# AfternoonCape_RevA3_6chan.net
KiCad netlist of a schematic drawn in Altium Designer
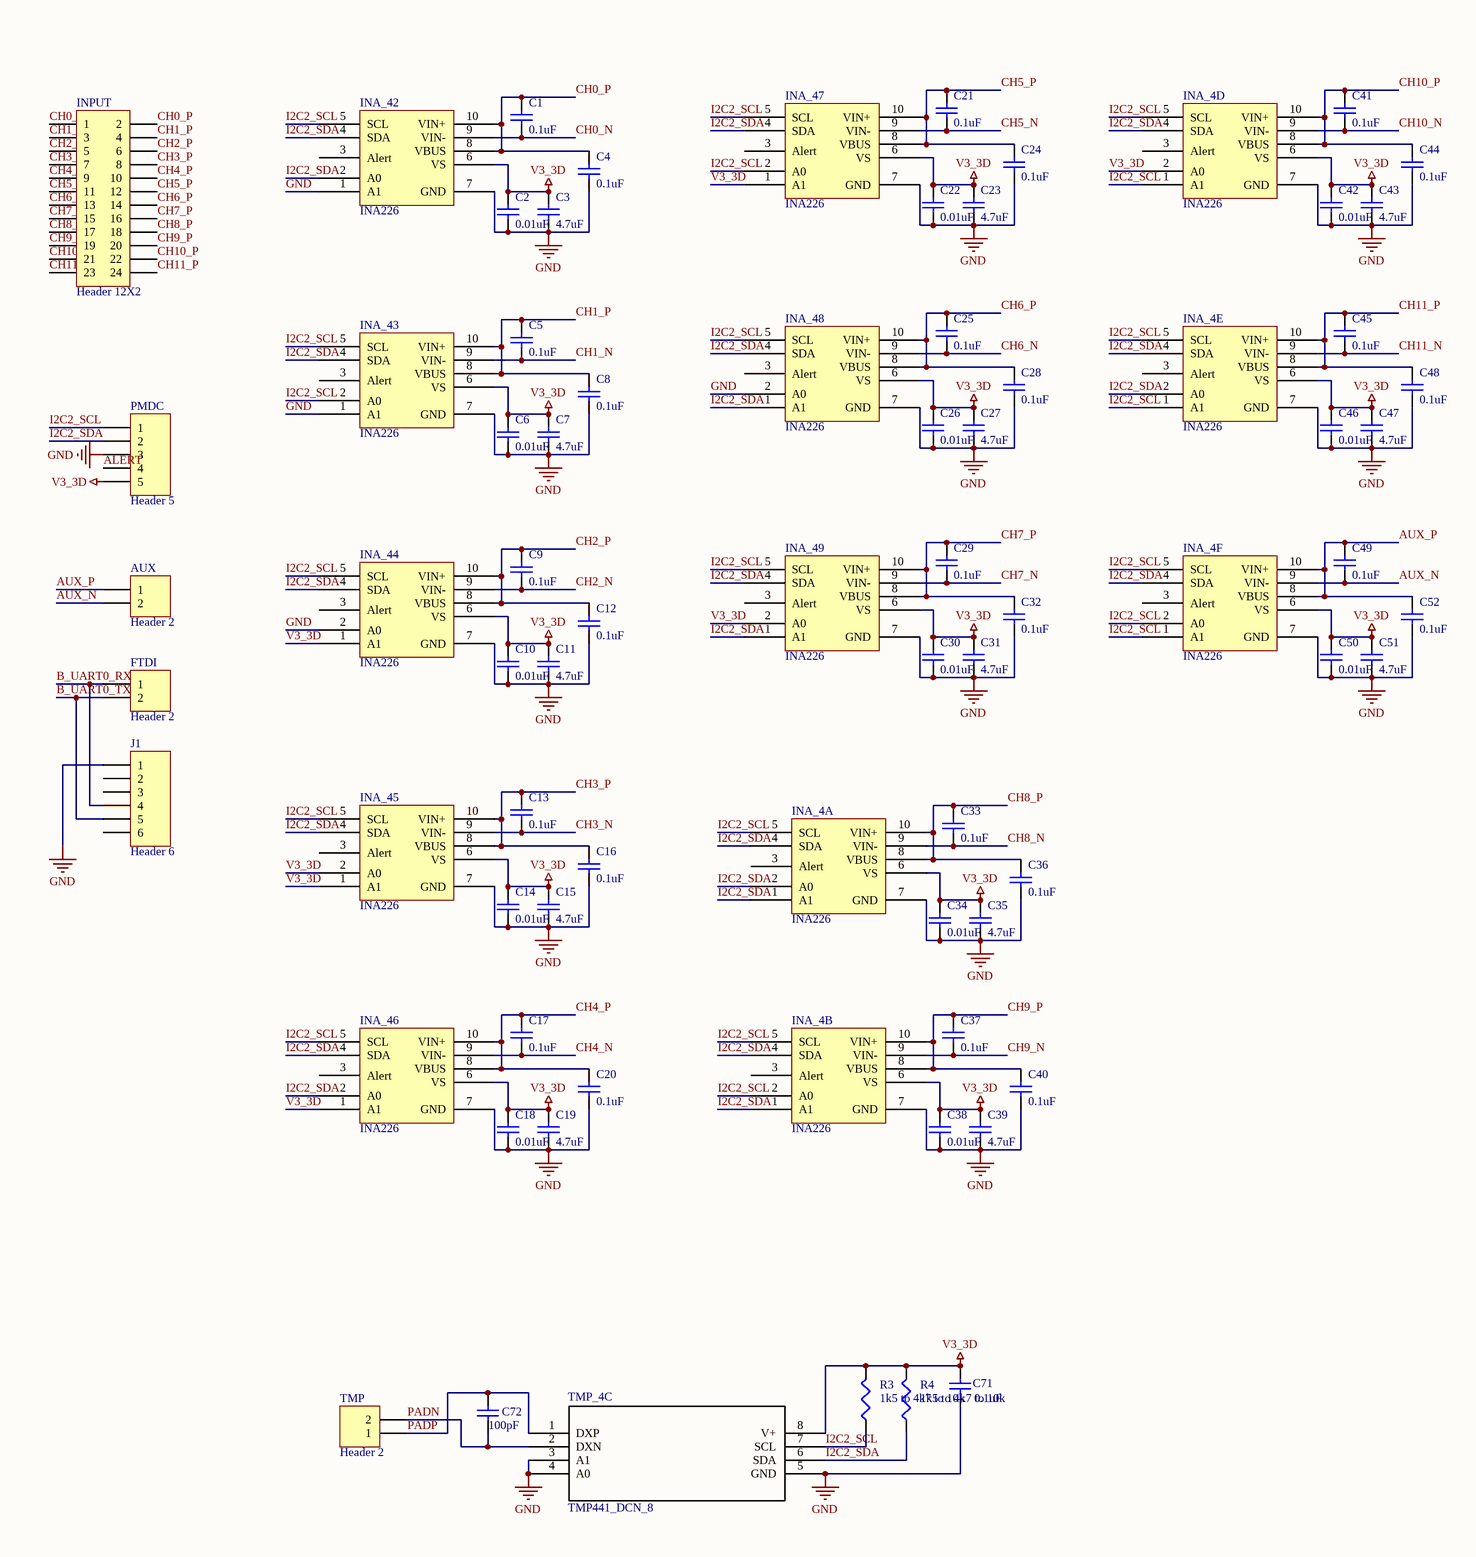
[diagram p0: AfternoonCape_RevA3_6chan.SchDoc, left]
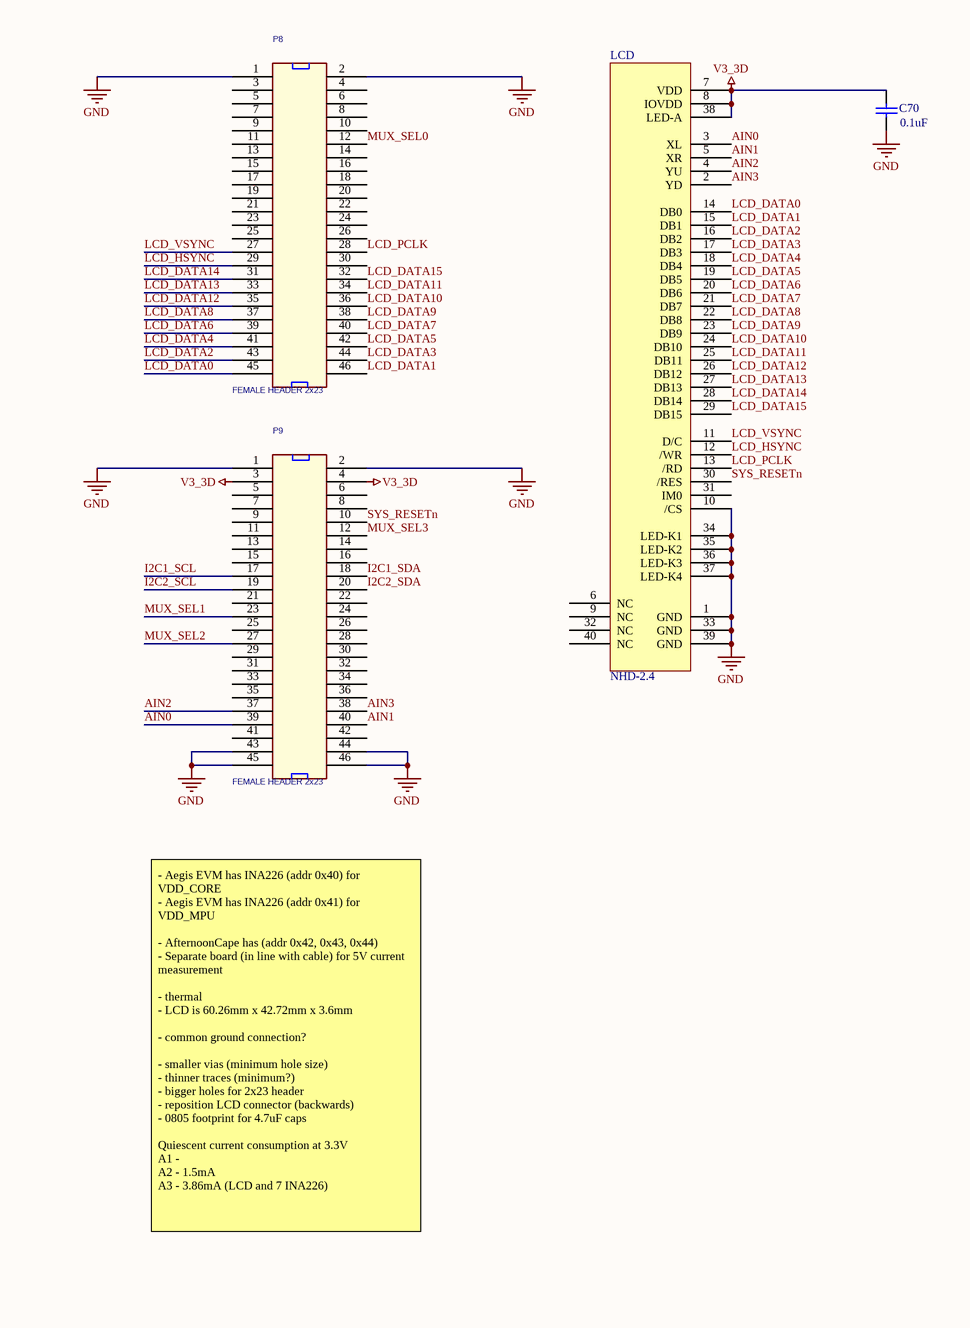
[diagram p1: AfternoonCape_RevA3_6chan.SchDoc, right]

(export (version "E")
  (design (tool "Eeschema 10.0.6"))
  (components
    (comp (ref "AUX")
      (value "Header 2")
      (footprint "HDR1X2")
      (description "Header, 2-Pin")
      (fields (field (name "PUBLISHER") "Altium Limited"))
      (libsource (lib "Miscellaneous Connectors") (part "Header 2"))
    )
    (comp (ref "C1")
      (value "0.1uF")
      (footprint "0402")
      (description "Capacitor (Semiconductor SIM Model)")
      (fields (field (name "Comment") "Cap Semi") (field (name "PUBLISHER") "Altium Limited"))
      (libsource (lib "Miscellaneous Devices") (part "Cap Semi"))
    )
    (comp (ref "C2")
      (value "0.01uF")
      (footprint "0402")
      (description "Capacitor (Semiconductor SIM Model)")
      (fields (field (name "Comment") "Cap Semi") (field (name "PUBLISHER") "Altium Limited"))
      (libsource (lib "Miscellaneous Devices") (part "Cap Semi"))
    )
    (comp (ref "C3")
      (value "4.7uF")
      (footprint "0402")
      (description "Capacitor (Semiconductor SIM Model)")
      (fields (field (name "Comment") "Cap Semi") (field (name "PUBLISHER") "Altium Limited"))
      (libsource (lib "Miscellaneous Devices") (part "Cap Semi"))
    )
    (comp (ref "C4")
      (value "0.1uF")
      (footprint "0402")
      (description "Capacitor (Semiconductor SIM Model)")
      (fields (field (name "Comment") "Cap Semi") (field (name "PUBLISHER") "Altium Limited"))
      (libsource (lib "Miscellaneous Devices") (part "Cap Semi"))
    )
    (comp (ref "C5")
      (value "0.1uF")
      (footprint "0402")
      (description "Capacitor (Semiconductor SIM Model)")
      (fields (field (name "Comment") "Cap Semi") (field (name "PUBLISHER") "Altium Limited"))
      (libsource (lib "Miscellaneous Devices") (part "Cap Semi"))
    )
    (comp (ref "C6")
      (value "0.01uF")
      (footprint "0402")
      (description "Capacitor (Semiconductor SIM Model)")
      (fields (field (name "Comment") "Cap Semi") (field (name "PUBLISHER") "Altium Limited"))
      (libsource (lib "Miscellaneous Devices") (part "Cap Semi"))
    )
    (comp (ref "C7")
      (value "4.7uF")
      (footprint "0402")
      (description "Capacitor (Semiconductor SIM Model)")
      (fields (field (name "Comment") "Cap Semi") (field (name "PUBLISHER") "Altium Limited"))
      (libsource (lib "Miscellaneous Devices") (part "Cap Semi"))
    )
    (comp (ref "C8")
      (value "0.1uF")
      (footprint "0402")
      (description "Capacitor (Semiconductor SIM Model)")
      (fields (field (name "Comment") "Cap Semi") (field (name "PUBLISHER") "Altium Limited"))
      (libsource (lib "Miscellaneous Devices") (part "Cap Semi"))
    )
    (comp (ref "C9")
      (value "0.1uF")
      (footprint "0402")
      (description "Capacitor (Semiconductor SIM Model)")
      (fields (field (name "Comment") "Cap Semi") (field (name "PUBLISHER") "Altium Limited"))
      (libsource (lib "Miscellaneous Devices") (part "Cap Semi"))
    )
    (comp (ref "C10")
      (value "0.01uF")
      (footprint "0402")
      (description "Capacitor (Semiconductor SIM Model)")
      (fields (field (name "Comment") "Cap Semi") (field (name "PUBLISHER") "Altium Limited"))
      (libsource (lib "Miscellaneous Devices") (part "Cap Semi"))
    )
    (comp (ref "C11")
      (value "4.7uF")
      (footprint "0402")
      (description "Capacitor (Semiconductor SIM Model)")
      (fields (field (name "Comment") "Cap Semi") (field (name "PUBLISHER") "Altium Limited"))
      (libsource (lib "Miscellaneous Devices") (part "Cap Semi"))
    )
    (comp (ref "C12")
      (value "0.1uF")
      (footprint "0402")
      (description "Capacitor (Semiconductor SIM Model)")
      (fields (field (name "Comment") "Cap Semi") (field (name "PUBLISHER") "Altium Limited"))
      (libsource (lib "Miscellaneous Devices") (part "Cap Semi"))
    )
    (comp (ref "C13")
      (value "0.1uF")
      (footprint "0402")
      (description "Capacitor (Semiconductor SIM Model)")
      (fields (field (name "Comment") "Cap Semi") (field (name "PUBLISHER") "Altium Limited"))
      (libsource (lib "Miscellaneous Devices") (part "Cap Semi"))
    )
    (comp (ref "C14")
      (value "0.01uF")
      (footprint "0402")
      (description "Capacitor (Semiconductor SIM Model)")
      (fields (field (name "Comment") "Cap Semi") (field (name "PUBLISHER") "Altium Limited"))
      (libsource (lib "Miscellaneous Devices") (part "Cap Semi"))
    )
    (comp (ref "C15")
      (value "4.7uF")
      (footprint "0402")
      (description "Capacitor (Semiconductor SIM Model)")
      (fields (field (name "Comment") "Cap Semi") (field (name "PUBLISHER") "Altium Limited"))
      (libsource (lib "Miscellaneous Devices") (part "Cap Semi"))
    )
    (comp (ref "C16")
      (value "0.1uF")
      (footprint "0402")
      (description "Capacitor (Semiconductor SIM Model)")
      (fields (field (name "Comment") "Cap Semi") (field (name "PUBLISHER") "Altium Limited"))
      (libsource (lib "Miscellaneous Devices") (part "Cap Semi"))
    )
    (comp (ref "C17")
      (value "0.1uF")
      (footprint "0402")
      (description "Capacitor (Semiconductor SIM Model)")
      (fields (field (name "Comment") "Cap Semi") (field (name "PUBLISHER") "Altium Limited"))
      (libsource (lib "Miscellaneous Devices") (part "Cap Semi"))
    )
    (comp (ref "C18")
      (value "0.01uF")
      (footprint "0402")
      (description "Capacitor (Semiconductor SIM Model)")
      (fields (field (name "Comment") "Cap Semi") (field (name "PUBLISHER") "Altium Limited"))
      (libsource (lib "Miscellaneous Devices") (part "Cap Semi"))
    )
    (comp (ref "C19")
      (value "4.7uF")
      (footprint "0402")
      (description "Capacitor (Semiconductor SIM Model)")
      (fields (field (name "Comment") "Cap Semi") (field (name "PUBLISHER") "Altium Limited"))
      (libsource (lib "Miscellaneous Devices") (part "Cap Semi"))
    )
    (comp (ref "C20")
      (value "0.1uF")
      (footprint "0402")
      (description "Capacitor (Semiconductor SIM Model)")
      (fields (field (name "Comment") "Cap Semi") (field (name "PUBLISHER") "Altium Limited"))
      (libsource (lib "Miscellaneous Devices") (part "Cap Semi"))
    )
    (comp (ref "C21")
      (value "0.1uF")
      (footprint "0402")
      (description "Capacitor (Semiconductor SIM Model)")
      (fields (field (name "Comment") "Cap Semi") (field (name "PUBLISHER") "Altium Limited"))
      (libsource (lib "Miscellaneous Devices") (part "Cap Semi"))
    )
    (comp (ref "C22")
      (value "0.01uF")
      (footprint "0402")
      (description "Capacitor (Semiconductor SIM Model)")
      (fields (field (name "Comment") "Cap Semi") (field (name "PUBLISHER") "Altium Limited"))
      (libsource (lib "Miscellaneous Devices") (part "Cap Semi"))
    )
    (comp (ref "C23")
      (value "4.7uF")
      (footprint "0402")
      (description "Capacitor (Semiconductor SIM Model)")
      (fields (field (name "Comment") "Cap Semi") (field (name "PUBLISHER") "Altium Limited"))
      (libsource (lib "Miscellaneous Devices") (part "Cap Semi"))
    )
    (comp (ref "C24")
      (value "0.1uF")
      (footprint "0402")
      (description "Capacitor (Semiconductor SIM Model)")
      (fields (field (name "Comment") "Cap Semi") (field (name "PUBLISHER") "Altium Limited"))
      (libsource (lib "Miscellaneous Devices") (part "Cap Semi"))
    )
    (comp (ref "C25")
      (value "0.1uF")
      (footprint "0402")
      (description "Capacitor (Semiconductor SIM Model)")
      (fields (field (name "Comment") "Cap Semi") (field (name "PUBLISHER") "Altium Limited"))
      (libsource (lib "Miscellaneous Devices") (part "Cap Semi"))
    )
    (comp (ref "C26")
      (value "0.01uF")
      (footprint "0402")
      (description "Capacitor (Semiconductor SIM Model)")
      (fields (field (name "Comment") "Cap Semi") (field (name "PUBLISHER") "Altium Limited"))
      (libsource (lib "Miscellaneous Devices") (part "Cap Semi"))
    )
    (comp (ref "C27")
      (value "4.7uF")
      (footprint "0402")
      (description "Capacitor (Semiconductor SIM Model)")
      (fields (field (name "Comment") "Cap Semi") (field (name "PUBLISHER") "Altium Limited"))
      (libsource (lib "Miscellaneous Devices") (part "Cap Semi"))
    )
    (comp (ref "C28")
      (value "0.1uF")
      (footprint "0402")
      (description "Capacitor (Semiconductor SIM Model)")
      (fields (field (name "Comment") "Cap Semi") (field (name "PUBLISHER") "Altium Limited"))
      (libsource (lib "Miscellaneous Devices") (part "Cap Semi"))
    )
    (comp (ref "C29")
      (value "0.1uF")
      (footprint "0402")
      (description "Capacitor (Semiconductor SIM Model)")
      (fields (field (name "Comment") "Cap Semi") (field (name "PUBLISHER") "Altium Limited"))
      (libsource (lib "Miscellaneous Devices") (part "Cap Semi"))
    )
    (comp (ref "C30")
      (value "0.01uF")
      (footprint "0402")
      (description "Capacitor (Semiconductor SIM Model)")
      (fields (field (name "Comment") "Cap Semi") (field (name "PUBLISHER") "Altium Limited"))
      (libsource (lib "Miscellaneous Devices") (part "Cap Semi"))
    )
    (comp (ref "C31")
      (value "4.7uF")
      (footprint "0402")
      (description "Capacitor (Semiconductor SIM Model)")
      (fields (field (name "Comment") "Cap Semi") (field (name "PUBLISHER") "Altium Limited"))
      (libsource (lib "Miscellaneous Devices") (part "Cap Semi"))
    )
    (comp (ref "C32")
      (value "0.1uF")
      (footprint "0402")
      (description "Capacitor (Semiconductor SIM Model)")
      (fields (field (name "Comment") "Cap Semi") (field (name "PUBLISHER") "Altium Limited"))
      (libsource (lib "Miscellaneous Devices") (part "Cap Semi"))
    )
    (comp (ref "C33")
      (value "0.1uF")
      (footprint "0402")
      (description "Capacitor (Semiconductor SIM Model)")
      (fields (field (name "Comment") "Cap Semi") (field (name "PUBLISHER") "Altium Limited"))
      (libsource (lib "Miscellaneous Devices") (part "Cap Semi"))
    )
    (comp (ref "C34")
      (value "0.01uF")
      (footprint "0402")
      (description "Capacitor (Semiconductor SIM Model)")
      (fields (field (name "Comment") "Cap Semi") (field (name "PUBLISHER") "Altium Limited"))
      (libsource (lib "Miscellaneous Devices") (part "Cap Semi"))
    )
    (comp (ref "C35")
      (value "4.7uF")
      (footprint "0402")
      (description "Capacitor (Semiconductor SIM Model)")
      (fields (field (name "Comment") "Cap Semi") (field (name "PUBLISHER") "Altium Limited"))
      (libsource (lib "Miscellaneous Devices") (part "Cap Semi"))
    )
    (comp (ref "C36")
      (value "0.1uF")
      (footprint "0402")
      (description "Capacitor (Semiconductor SIM Model)")
      (fields (field (name "Comment") "Cap Semi") (field (name "PUBLISHER") "Altium Limited"))
      (libsource (lib "Miscellaneous Devices") (part "Cap Semi"))
    )
    (comp (ref "C37")
      (value "0.1uF")
      (footprint "0402")
      (description "Capacitor (Semiconductor SIM Model)")
      (fields (field (name "Comment") "Cap Semi") (field (name "PUBLISHER") "Altium Limited"))
      (libsource (lib "Miscellaneous Devices") (part "Cap Semi"))
    )
    (comp (ref "C38")
      (value "0.01uF")
      (footprint "0402")
      (description "Capacitor (Semiconductor SIM Model)")
      (fields (field (name "Comment") "Cap Semi") (field (name "PUBLISHER") "Altium Limited"))
      (libsource (lib "Miscellaneous Devices") (part "Cap Semi"))
    )
    (comp (ref "C39")
      (value "4.7uF")
      (footprint "0402")
      (description "Capacitor (Semiconductor SIM Model)")
      (fields (field (name "Comment") "Cap Semi") (field (name "PUBLISHER") "Altium Limited"))
      (libsource (lib "Miscellaneous Devices") (part "Cap Semi"))
    )
    (comp (ref "C40")
      (value "0.1uF")
      (footprint "0402")
      (description "Capacitor (Semiconductor SIM Model)")
      (fields (field (name "Comment") "Cap Semi") (field (name "PUBLISHER") "Altium Limited"))
      (libsource (lib "Miscellaneous Devices") (part "Cap Semi"))
    )
    (comp (ref "C41")
      (value "0.1uF")
      (footprint "0402")
      (description "Capacitor (Semiconductor SIM Model)")
      (fields (field (name "Comment") "Cap Semi") (field (name "PUBLISHER") "Altium Limited"))
      (libsource (lib "Miscellaneous Devices") (part "Cap Semi"))
    )
    (comp (ref "C42")
      (value "0.01uF")
      (footprint "0402")
      (description "Capacitor (Semiconductor SIM Model)")
      (fields (field (name "Comment") "Cap Semi") (field (name "PUBLISHER") "Altium Limited"))
      (libsource (lib "Miscellaneous Devices") (part "Cap Semi"))
    )
    (comp (ref "C43")
      (value "4.7uF")
      (footprint "0402")
      (description "Capacitor (Semiconductor SIM Model)")
      (fields (field (name "Comment") "Cap Semi") (field (name "PUBLISHER") "Altium Limited"))
      (libsource (lib "Miscellaneous Devices") (part "Cap Semi"))
    )
    (comp (ref "C44")
      (value "0.1uF")
      (footprint "0402")
      (description "Capacitor (Semiconductor SIM Model)")
      (fields (field (name "Comment") "Cap Semi") (field (name "PUBLISHER") "Altium Limited"))
      (libsource (lib "Miscellaneous Devices") (part "Cap Semi"))
    )
    (comp (ref "C45")
      (value "0.1uF")
      (footprint "0402")
      (description "Capacitor (Semiconductor SIM Model)")
      (fields (field (name "Comment") "Cap Semi") (field (name "PUBLISHER") "Altium Limited"))
      (libsource (lib "Miscellaneous Devices") (part "Cap Semi"))
    )
    (comp (ref "C46")
      (value "0.01uF")
      (footprint "0402")
      (description "Capacitor (Semiconductor SIM Model)")
      (fields (field (name "Comment") "Cap Semi") (field (name "PUBLISHER") "Altium Limited"))
      (libsource (lib "Miscellaneous Devices") (part "Cap Semi"))
    )
    (comp (ref "C47")
      (value "4.7uF")
      (footprint "0402")
      (description "Capacitor (Semiconductor SIM Model)")
      (fields (field (name "Comment") "Cap Semi") (field (name "PUBLISHER") "Altium Limited"))
      (libsource (lib "Miscellaneous Devices") (part "Cap Semi"))
    )
    (comp (ref "C48")
      (value "0.1uF")
      (footprint "0402")
      (description "Capacitor (Semiconductor SIM Model)")
      (fields (field (name "Comment") "Cap Semi") (field (name "PUBLISHER") "Altium Limited"))
      (libsource (lib "Miscellaneous Devices") (part "Cap Semi"))
    )
    (comp (ref "C49")
      (value "0.1uF")
      (footprint "0402")
      (description "Capacitor (Semiconductor SIM Model)")
      (fields (field (name "Comment") "Cap Semi") (field (name "PUBLISHER") "Altium Limited"))
      (libsource (lib "Miscellaneous Devices") (part "Cap Semi"))
    )
    (comp (ref "C50")
      (value "0.01uF")
      (footprint "0402")
      (description "Capacitor (Semiconductor SIM Model)")
      (fields (field (name "Comment") "Cap Semi") (field (name "PUBLISHER") "Altium Limited"))
      (libsource (lib "Miscellaneous Devices") (part "Cap Semi"))
    )
    (comp (ref "C51")
      (value "4.7uF")
      (footprint "0402")
      (description "Capacitor (Semiconductor SIM Model)")
      (fields (field (name "Comment") "Cap Semi") (field (name "PUBLISHER") "Altium Limited"))
      (libsource (lib "Miscellaneous Devices") (part "Cap Semi"))
    )
    (comp (ref "C52")
      (value "0.1uF")
      (footprint "0402")
      (description "Capacitor (Semiconductor SIM Model)")
      (fields (field (name "Comment") "Cap Semi") (field (name "PUBLISHER") "Altium Limited"))
      (libsource (lib "Miscellaneous Devices") (part "Cap Semi"))
    )
    (comp (ref "C70")
      (value "0.1uF")
      (footprint "0402")
      (description "Capacitor (Semiconductor SIM Model)")
      (fields (field (name "Comment") "Cap Semi") (field (name "PUBLISHER") "Altium Limited"))
      (libsource (lib "Miscellaneous Devices") (part "Cap Semi"))
    )
    (comp (ref "C71")
      (value "0.1uF")
      (footprint "0402")
      (description "Capacitor (Semiconductor SIM Model)")
      (fields (field (name "Comment") "Cap Semi") (field (name "PUBLISHER") "Altium Limited"))
      (libsource (lib "Miscellaneous Devices") (part "Cap Semi"))
    )
    (comp (ref "C72")
      (value "100pF")
      (footprint "0402")
      (description "Capacitor (Semiconductor SIM Model)")
      (fields (field (name "Comment") "Cap Semi") (field (name "PUBLISHER") "Altium Limited"))
      (libsource (lib "Miscellaneous Devices") (part "Cap Semi"))
    )
    (comp (ref "FTDI")
      (value "Header 2")
      (footprint "HDR1X2")
      (description "Header, 2-Pin")
      (fields (field (name "PUBLISHER") "Altium Limited"))
      (libsource (lib "Miscellaneous Connectors") (part "Header 2"))
    )
    (comp (ref "INA_4A") (value "INA226") (footprint "DGS10") (libsource (lib "INA226") (part "INA226")))
    (comp (ref "INA_4B") (value "INA226") (footprint "DGS10") (libsource (lib "INA226") (part "INA226")))
    (comp (ref "INA_4D") (value "INA226") (footprint "DGS10") (libsource (lib "INA226") (part "INA226")))
    (comp (ref "INA_4E") (value "INA226") (footprint "DGS10") (libsource (lib "INA226") (part "INA226")))
    (comp (ref "INA_4F") (value "INA226") (footprint "DGS10") (libsource (lib "INA226") (part "INA226")))
    (comp (ref "INA_42") (value "INA226") (footprint "DGS10") (libsource (lib "INA226") (part "INA226")))
    (comp (ref "INA_43") (value "INA226") (footprint "DGS10") (libsource (lib "INA226") (part "INA226")))
    (comp (ref "INA_44") (value "INA226") (footprint "DGS10") (libsource (lib "INA226") (part "INA226")))
    (comp (ref "INA_45") (value "INA226") (footprint "DGS10") (libsource (lib "INA226") (part "INA226")))
    (comp (ref "INA_46") (value "INA226") (footprint "DGS10") (libsource (lib "INA226") (part "INA226")))
    (comp (ref "INA_47") (value "INA226") (footprint "DGS10") (libsource (lib "INA226") (part "INA226")))
    (comp (ref "INA_48") (value "INA226") (footprint "DGS10") (libsource (lib "INA226") (part "INA226")))
    (comp (ref "INA_49") (value "INA226") (footprint "DGS10") (libsource (lib "INA226") (part "INA226")))
    (comp (ref "INPUT")
      (value "Header 12X2")
      (footprint "HDR2X12")
      (description "Header, 12-Pin, Dual row")
      (fields (field (name "PUBLISHER") "Altium Limited"))
      (libsource (lib "Miscellaneous Connectors") (part "Header 12X2"))
    )
    (comp (ref "J1")
      (value "Header 6")
      (footprint "HDR1X6")
      (description "6-pin female header, long legs for FTDI-USB cable")
      (fields (field (name "PUBLISHER") "Altium Limited"))
      (libsource (lib "Miscellaneous Connectors") (part "Header 6"))
    )
    (comp (ref "LCD")
      (value "NHD-2.4")
      (footprint "NHD-2.4")
      (description "2.4\" LCD NHD-2.4-240320SF-CTXL#-FTN1 54132-4062 Molex LCD Connector Footprint")
      (libsource (lib "Sitara_PowerMonitorCape") (part "NHD-2.4"))
    )
    (comp (ref "P8")
      (value "FEMALE HEADER 2x23")
      (description "CONN HEADER FMAL 46PS.1\" DL GOLD")
      (fields
        (field (name "MANUFACTURER") "Sullins Connector Solutions")
        (field (name "MANUFACTURER PART NUMBER") "PPPC232LFBN-RC")
      )
      (libsource (lib "BEAGLEBONEBLACK_REV A5B") (part "HDR_46_F_2_0.1_0.1"))
    )
    (comp (ref "P9")
      (value "FEMALE HEADER 2x23")
      (description "CONN HEADER FMAL 46PS.1\" DL GOLD")
      (fields
        (field (name "MANUFACTURER") "Sullins Connector Solutions")
        (field (name "MANUFACTURER PART NUMBER") "PPPC232LFBN-RC")
      )
      (libsource (lib "BEAGLEBONEBLACK_REV A5B") (part "HDR_46_F_2_0.1_0.1"))
    )
    (comp (ref "PMDC")
      (value "Header 5")
      (footprint "HDR1X5")
      (description "Header, 5-Pin")
      (fields (field (name "PUBLISHER") "Altium Limited"))
      (libsource (lib "Miscellaneous Connectors") (part "Header 5"))
    )
    (comp (ref "R3")
      (value "1k5 to 4k7 to 10k")
      (footprint "0402")
      (description "Resistor")
      (fields (field (name "Comment") "Res3") (field (name "PUBLISHER") "Altium Limited"))
      (libsource (lib "Miscellaneous Devices") (part "Res3"))
    )
    (comp (ref "R4")
      (value "1k5 to 4k7 to 10k")
      (footprint "0402")
      (description "Resistor")
      (fields (field (name "Comment") "Res3") (field (name "PUBLISHER") "Altium Limited"))
      (libsource (lib "Miscellaneous Devices") (part "Res3"))
    )
    (comp (ref "TMP")
      (value "Header 2")
      (footprint "HDR1X2")
      (description "Header, 2-Pin")
      (fields (field (name "PUBLISHER") "Altium Limited"))
      (libsource (lib "") (part "Header 2_1"))
    )
    (comp (ref "TMP_4C")
      (value "TMP441_DCN_8")
      (footprint "TMP441:DCN8-L")
      (description "Imported")
      (fields
        (field (name "MANUFACTURER_PART_NUMBER") "tmp441_dcn_8")
        (field (name "GENERIC_PART_NUMBER") "TMP441")
      )
      (libsource (lib "TMP441") (part "TMP441_DCN_8"))
    )
  )
  (nets
    (net (code "1") (name "/AIN0") (class "Default")
      (node (ref "LCD") (pin "3") (pinfunction "XL_3") (pintype "passive"))
      (node (ref "P9") (pin "39") (pinfunction "20_39") (pintype "passive"))
    )
    (net (code "2") (name "/AIN1") (class "Default")
      (node (ref "LCD") (pin "5") (pinfunction "XR_5") (pintype "passive"))
      (node (ref "P9") (pin "40") (pinfunction "45_40") (pintype "passive"))
    )
    (net (code "3") (name "/AIN2") (class "Default")
      (node (ref "LCD") (pin "4") (pinfunction "YU_4") (pintype "passive"))
      (node (ref "P9") (pin "37") (pinfunction "19_37") (pintype "passive"))
    )
    (net (code "4") (name "/AIN3") (class "Default")
      (node (ref "LCD") (pin "2") (pinfunction "YD_2") (pintype "passive"))
      (node (ref "P9") (pin "38") (pinfunction "44_38") (pintype "passive"))
    )
    (net (code "5") (name "/ALERT") (class "Default")
      (node (ref "PMDC") (pin "4") (pinfunction "4_4") (pintype "passive"))
    )
    (net (code "6") (name "/AUX_N") (class "Default")
      (node (ref "AUX") (pin "2") (pinfunction "2_2") (pintype "passive"))
      (node (ref "C49") (pin "1") (pinfunction "1_1") (pintype "passive"))
      (node (ref "INA_4F") (pin "9") (pinfunction "VIN-_9") (pintype "passive"))
    )
    (net (code "7") (name "/AUX_P") (class "Default")
      (node (ref "AUX") (pin "1") (pinfunction "1_1") (pintype "passive"))
      (node (ref "C49") (pin "2") (pinfunction "2_2") (pintype "passive"))
      (node (ref "C52") (pin "2") (pinfunction "2_2") (pintype "passive"))
      (node (ref "INA_4F") (pin "10") (pinfunction "VIN+_10") (pintype "passive"))
      (node (ref "INA_4F") (pin "8") (pinfunction "VBUS_8") (pintype "passive"))
    )
    (net (code "8") (name "/B_UART0_RX") (class "Default")
      (node (ref "FTDI") (pin "1") (pinfunction "1_1") (pintype "passive"))
      (node (ref "J1") (pin "4") (pinfunction "4_4") (pintype "passive"))
    )
    (net (code "9") (name "/B_UART0_TX") (class "Default")
      (node (ref "FTDI") (pin "2") (pinfunction "2_2") (pintype "passive"))
      (node (ref "J1") (pin "5") (pinfunction "5_5") (pintype "passive"))
    )
    (net (code "10") (name "/CH0_N") (class "Default")
      (node (ref "C1") (pin "1") (pinfunction "1_1") (pintype "passive"))
      (node (ref "INA_42") (pin "9") (pinfunction "VIN-_9") (pintype "passive"))
      (node (ref "INPUT") (pin "1") (pinfunction "1_1") (pintype "passive"))
    )
    (net (code "11") (name "/CH0_P") (class "Default")
      (node (ref "C1") (pin "2") (pinfunction "2_2") (pintype "passive"))
      (node (ref "C4") (pin "2") (pinfunction "2_2") (pintype "passive"))
      (node (ref "INA_42") (pin "10") (pinfunction "VIN+_10") (pintype "passive"))
      (node (ref "INA_42") (pin "8") (pinfunction "VBUS_8") (pintype "passive"))
      (node (ref "INPUT") (pin "2") (pinfunction "2_2") (pintype "passive"))
    )
    (net (code "12") (name "/CH1_N") (class "Default")
      (node (ref "C5") (pin "1") (pinfunction "1_1") (pintype "passive"))
      (node (ref "INA_43") (pin "9") (pinfunction "VIN-_9") (pintype "passive"))
      (node (ref "INPUT") (pin "3") (pinfunction "3_3") (pintype "passive"))
    )
    (net (code "13") (name "/CH1_P") (class "Default")
      (node (ref "C5") (pin "2") (pinfunction "2_2") (pintype "passive"))
      (node (ref "C8") (pin "2") (pinfunction "2_2") (pintype "passive"))
      (node (ref "INA_43") (pin "10") (pinfunction "VIN+_10") (pintype "passive"))
      (node (ref "INA_43") (pin "8") (pinfunction "VBUS_8") (pintype "passive"))
      (node (ref "INPUT") (pin "4") (pinfunction "4_4") (pintype "passive"))
    )
    (net (code "14") (name "/CH2_N") (class "Default")
      (node (ref "C9") (pin "1") (pinfunction "1_1") (pintype "passive"))
      (node (ref "INA_44") (pin "9") (pinfunction "VIN-_9") (pintype "passive"))
      (node (ref "INPUT") (pin "5") (pinfunction "5_5") (pintype "passive"))
    )
    (net (code "15") (name "/CH2_P") (class "Default")
      (node (ref "C12") (pin "2") (pinfunction "2_2") (pintype "passive"))
      (node (ref "C9") (pin "2") (pinfunction "2_2") (pintype "passive"))
      (node (ref "INA_44") (pin "10") (pinfunction "VIN+_10") (pintype "passive"))
      (node (ref "INA_44") (pin "8") (pinfunction "VBUS_8") (pintype "passive"))
      (node (ref "INPUT") (pin "6") (pinfunction "6_6") (pintype "passive"))
    )
    (net (code "16") (name "/CH3_N") (class "Default")
      (node (ref "C13") (pin "1") (pinfunction "1_1") (pintype "passive"))
      (node (ref "INA_45") (pin "9") (pinfunction "VIN-_9") (pintype "passive"))
      (node (ref "INPUT") (pin "7") (pinfunction "7_7") (pintype "passive"))
    )
    (net (code "17") (name "/CH3_P") (class "Default")
      (node (ref "C13") (pin "2") (pinfunction "2_2") (pintype "passive"))
      (node (ref "C16") (pin "2") (pinfunction "2_2") (pintype "passive"))
      (node (ref "INA_45") (pin "10") (pinfunction "VIN+_10") (pintype "passive"))
      (node (ref "INA_45") (pin "8") (pinfunction "VBUS_8") (pintype "passive"))
      (node (ref "INPUT") (pin "8") (pinfunction "8_8") (pintype "passive"))
    )
    (net (code "18") (name "/CH4_N") (class "Default")
      (node (ref "C17") (pin "1") (pinfunction "1_1") (pintype "passive"))
      (node (ref "INA_46") (pin "9") (pinfunction "VIN-_9") (pintype "passive"))
      (node (ref "INPUT") (pin "9") (pinfunction "9_9") (pintype "passive"))
    )
    (net (code "19") (name "/CH4_P") (class "Default")
      (node (ref "C17") (pin "2") (pinfunction "2_2") (pintype "passive"))
      (node (ref "C20") (pin "2") (pinfunction "2_2") (pintype "passive"))
      (node (ref "INA_46") (pin "10") (pinfunction "VIN+_10") (pintype "passive"))
      (node (ref "INA_46") (pin "8") (pinfunction "VBUS_8") (pintype "passive"))
      (node (ref "INPUT") (pin "10") (pinfunction "10_10") (pintype "passive"))
    )
    (net (code "20") (name "/CH5_N") (class "Default")
      (node (ref "C21") (pin "1") (pinfunction "1_1") (pintype "passive"))
      (node (ref "INA_47") (pin "9") (pinfunction "VIN-_9") (pintype "passive"))
      (node (ref "INPUT") (pin "11") (pinfunction "11_11") (pintype "passive"))
    )
    (net (code "21") (name "/CH5_P") (class "Default")
      (node (ref "C21") (pin "2") (pinfunction "2_2") (pintype "passive"))
      (node (ref "C24") (pin "2") (pinfunction "2_2") (pintype "passive"))
      (node (ref "INA_47") (pin "10") (pinfunction "VIN+_10") (pintype "passive"))
      (node (ref "INA_47") (pin "8") (pinfunction "VBUS_8") (pintype "passive"))
      (node (ref "INPUT") (pin "12") (pinfunction "12_12") (pintype "passive"))
    )
    (net (code "22") (name "/CH6_N") (class "Default")
      (node (ref "C25") (pin "1") (pinfunction "1_1") (pintype "passive"))
      (node (ref "INA_48") (pin "9") (pinfunction "VIN-_9") (pintype "passive"))
      (node (ref "INPUT") (pin "13") (pinfunction "13_13") (pintype "passive"))
    )
    (net (code "23") (name "/CH6_P") (class "Default")
      (node (ref "C25") (pin "2") (pinfunction "2_2") (pintype "passive"))
      (node (ref "C28") (pin "2") (pinfunction "2_2") (pintype "passive"))
      (node (ref "INA_48") (pin "10") (pinfunction "VIN+_10") (pintype "passive"))
      (node (ref "INA_48") (pin "8") (pinfunction "VBUS_8") (pintype "passive"))
      (node (ref "INPUT") (pin "14") (pinfunction "14_14") (pintype "passive"))
    )
    (net (code "24") (name "/CH7_N") (class "Default")
      (node (ref "C29") (pin "1") (pinfunction "1_1") (pintype "passive"))
      (node (ref "INA_49") (pin "9") (pinfunction "VIN-_9") (pintype "passive"))
      (node (ref "INPUT") (pin "15") (pinfunction "15_15") (pintype "passive"))
    )
    (net (code "25") (name "/CH7_P") (class "Default")
      (node (ref "C29") (pin "2") (pinfunction "2_2") (pintype "passive"))
      (node (ref "C32") (pin "2") (pinfunction "2_2") (pintype "passive"))
      (node (ref "INA_49") (pin "10") (pinfunction "VIN+_10") (pintype "passive"))
      (node (ref "INA_49") (pin "8") (pinfunction "VBUS_8") (pintype "passive"))
      (node (ref "INPUT") (pin "16") (pinfunction "16_16") (pintype "passive"))
    )
    (net (code "26") (name "/CH8_N") (class "Default")
      (node (ref "C33") (pin "1") (pinfunction "1_1") (pintype "passive"))
      (node (ref "INA_4A") (pin "9") (pinfunction "VIN-_9") (pintype "passive"))
      (node (ref "INPUT") (pin "17") (pinfunction "17_17") (pintype "passive"))
    )
    (net (code "27") (name "/CH8_P") (class "Default")
      (node (ref "C33") (pin "2") (pinfunction "2_2") (pintype "passive"))
      (node (ref "C36") (pin "2") (pinfunction "2_2") (pintype "passive"))
      (node (ref "INA_4A") (pin "10") (pinfunction "VIN+_10") (pintype "passive"))
      (node (ref "INA_4A") (pin "8") (pinfunction "VBUS_8") (pintype "passive"))
      (node (ref "INPUT") (pin "18") (pinfunction "18_18") (pintype "passive"))
    )
    (net (code "28") (name "/CH9_N") (class "Default")
      (node (ref "C37") (pin "1") (pinfunction "1_1") (pintype "passive"))
      (node (ref "INA_4B") (pin "9") (pinfunction "VIN-_9") (pintype "passive"))
      (node (ref "INPUT") (pin "19") (pinfunction "19_19") (pintype "passive"))
    )
    (net (code "29") (name "/CH9_P") (class "Default")
      (node (ref "C37") (pin "2") (pinfunction "2_2") (pintype "passive"))
      (node (ref "C40") (pin "2") (pinfunction "2_2") (pintype "passive"))
      (node (ref "INA_4B") (pin "10") (pinfunction "VIN+_10") (pintype "passive"))
      (node (ref "INA_4B") (pin "8") (pinfunction "VBUS_8") (pintype "passive"))
      (node (ref "INPUT") (pin "20") (pinfunction "20_20") (pintype "passive"))
    )
    (net (code "30") (name "/CH10_N") (class "Default")
      (node (ref "C41") (pin "1") (pinfunction "1_1") (pintype "passive"))
      (node (ref "INA_4D") (pin "9") (pinfunction "VIN-_9") (pintype "passive"))
      (node (ref "INPUT") (pin "21") (pinfunction "21_21") (pintype "passive"))
    )
    (net (code "31") (name "/CH10_P") (class "Default")
      (node (ref "C41") (pin "2") (pinfunction "2_2") (pintype "passive"))
      (node (ref "C44") (pin "2") (pinfunction "2_2") (pintype "passive"))
      (node (ref "INA_4D") (pin "10") (pinfunction "VIN+_10") (pintype "passive"))
      (node (ref "INA_4D") (pin "8") (pinfunction "VBUS_8") (pintype "passive"))
      (node (ref "INPUT") (pin "22") (pinfunction "22_22") (pintype "passive"))
    )
    (net (code "32") (name "/CH11_N") (class "Default")
      (node (ref "C45") (pin "1") (pinfunction "1_1") (pintype "passive"))
      (node (ref "INA_4E") (pin "9") (pinfunction "VIN-_9") (pintype "passive"))
      (node (ref "INPUT") (pin "23") (pinfunction "23_23") (pintype "passive"))
    )
    (net (code "33") (name "/CH11_P") (class "Default")
      (node (ref "C45") (pin "2") (pinfunction "2_2") (pintype "passive"))
      (node (ref "C48") (pin "2") (pinfunction "2_2") (pintype "passive"))
      (node (ref "INA_4E") (pin "10") (pinfunction "VIN+_10") (pintype "passive"))
      (node (ref "INA_4E") (pin "8") (pinfunction "VBUS_8") (pintype "passive"))
      (node (ref "INPUT") (pin "24") (pinfunction "24_24") (pintype "passive"))
    )
    (net (code "34") (name "/I2C1_SCL") (class "Default")
      (node (ref "P9") (pin "17") (pinfunction "9_17") (pintype "passive"))
    )
    (net (code "35") (name "/I2C1_SDA") (class "Default")
      (node (ref "P9") (pin "18") (pinfunction "34_18") (pintype "passive"))
    )
    (net (code "36") (name "/I2C2_SCL") (class "Default")
      (node (ref "INA_42") (pin "5") (pinfunction "SCL_5") (pintype "passive"))
      (node (ref "INA_43") (pin "2") (pinfunction "A0_2") (pintype "passive"))
      (node (ref "INA_43") (pin "5") (pinfunction "SCL_5") (pintype "passive"))
      (node (ref "INA_44") (pin "5") (pinfunction "SCL_5") (pintype "passive"))
      (node (ref "INA_45") (pin "5") (pinfunction "SCL_5") (pintype "passive"))
      (node (ref "INA_46") (pin "5") (pinfunction "SCL_5") (pintype "passive"))
      (node (ref "INA_47") (pin "2") (pinfunction "A0_2") (pintype "passive"))
      (node (ref "INA_47") (pin "5") (pinfunction "SCL_5") (pintype "passive"))
      (node (ref "INA_48") (pin "5") (pinfunction "SCL_5") (pintype "passive"))
      (node (ref "INA_49") (pin "5") (pinfunction "SCL_5") (pintype "passive"))
      (node (ref "INA_4A") (pin "5") (pinfunction "SCL_5") (pintype "passive"))
      (node (ref "INA_4B") (pin "2") (pinfunction "A0_2") (pintype "passive"))
      (node (ref "INA_4B") (pin "5") (pinfunction "SCL_5") (pintype "passive"))
      (node (ref "INA_4D") (pin "1") (pinfunction "A1_1") (pintype "passive"))
      (node (ref "INA_4D") (pin "5") (pinfunction "SCL_5") (pintype "passive"))
      (node (ref "INA_4E") (pin "1") (pinfunction "A1_1") (pintype "passive"))
      (node (ref "INA_4E") (pin "5") (pinfunction "SCL_5") (pintype "passive"))
      (node (ref "INA_4F") (pin "1") (pinfunction "A1_1") (pintype "passive"))
      (node (ref "INA_4F") (pin "2") (pinfunction "A0_2") (pintype "passive"))
      (node (ref "INA_4F") (pin "5") (pinfunction "SCL_5") (pintype "passive"))
      (node (ref "P9") (pin "19") (pinfunction "10_19") (pintype "passive"))
      (node (ref "PMDC") (pin "1") (pinfunction "1_1") (pintype "passive"))
      (node (ref "R3") (pin "1") (pinfunction "1_1") (pintype "passive"))
      (node (ref "TMP_4C") (pin "7") (pinfunction "SCL_7") (pintype "passive"))
    )
    (net (code "37") (name "/I2C2_SDA") (class "Default")
      (node (ref "INA_42") (pin "2") (pinfunction "A0_2") (pintype "passive"))
      (node (ref "INA_42") (pin "4") (pinfunction "SDA_4") (pintype "passive"))
      (node (ref "INA_43") (pin "4") (pinfunction "SDA_4") (pintype "passive"))
      (node (ref "INA_44") (pin "4") (pinfunction "SDA_4") (pintype "passive"))
      (node (ref "INA_45") (pin "4") (pinfunction "SDA_4") (pintype "passive"))
      (node (ref "INA_46") (pin "2") (pinfunction "A0_2") (pintype "passive"))
      (node (ref "INA_46") (pin "4") (pinfunction "SDA_4") (pintype "passive"))
      (node (ref "INA_47") (pin "4") (pinfunction "SDA_4") (pintype "passive"))
      (node (ref "INA_48") (pin "1") (pinfunction "A1_1") (pintype "passive"))
      (node (ref "INA_48") (pin "4") (pinfunction "SDA_4") (pintype "passive"))
      (node (ref "INA_49") (pin "1") (pinfunction "A1_1") (pintype "passive"))
      (node (ref "INA_49") (pin "4") (pinfunction "SDA_4") (pintype "passive"))
      (node (ref "INA_4A") (pin "1") (pinfunction "A1_1") (pintype "passive"))
      (node (ref "INA_4A") (pin "2") (pinfunction "A0_2") (pintype "passive"))
      (node (ref "INA_4A") (pin "4") (pinfunction "SDA_4") (pintype "passive"))
      (node (ref "INA_4B") (pin "1") (pinfunction "A1_1") (pintype "passive"))
      (node (ref "INA_4B") (pin "4") (pinfunction "SDA_4") (pintype "passive"))
      (node (ref "INA_4D") (pin "4") (pinfunction "SDA_4") (pintype "passive"))
      (node (ref "INA_4E") (pin "2") (pinfunction "A0_2") (pintype "passive"))
      (node (ref "INA_4E") (pin "4") (pinfunction "SDA_4") (pintype "passive"))
      (node (ref "INA_4F") (pin "4") (pinfunction "SDA_4") (pintype "passive"))
      (node (ref "P9") (pin "20") (pinfunction "35_20") (pintype "passive"))
      (node (ref "PMDC") (pin "2") (pinfunction "2_2") (pintype "passive"))
      (node (ref "R4") (pin "1") (pinfunction "1_1") (pintype "passive"))
      (node (ref "TMP_4C") (pin "6") (pinfunction "SDA_6") (pintype "passive"))
    )
    (net (code "38") (name "/LCD_DATA0") (class "Default")
      (node (ref "LCD") (pin "14") (pinfunction "DB0_14") (pintype "passive"))
      (node (ref "P8") (pin "45") (pinfunction "23_45") (pintype "passive"))
    )
    (net (code "39") (name "/LCD_DATA1") (class "Default")
      (node (ref "LCD") (pin "15") (pinfunction "DB1_15") (pintype "passive"))
      (node (ref "P8") (pin "46") (pinfunction "48_46") (pintype "passive"))
    )
    (net (code "40") (name "/LCD_DATA2") (class "Default")
      (node (ref "LCD") (pin "16") (pinfunction "DB2_16") (pintype "passive"))
      (node (ref "P8") (pin "43") (pinfunction "22_43") (pintype "passive"))
    )
    (net (code "41") (name "/LCD_DATA3") (class "Default")
      (node (ref "LCD") (pin "17") (pinfunction "DB3_17") (pintype "passive"))
      (node (ref "P8") (pin "44") (pinfunction "47_44") (pintype "passive"))
    )
    (net (code "42") (name "/LCD_DATA4") (class "Default")
      (node (ref "LCD") (pin "18") (pinfunction "DB4_18") (pintype "passive"))
      (node (ref "P8") (pin "41") (pinfunction "21_41") (pintype "passive"))
    )
    (net (code "43") (name "/LCD_DATA5") (class "Default")
      (node (ref "LCD") (pin "19") (pinfunction "DB5_19") (pintype "passive"))
      (node (ref "P8") (pin "42") (pinfunction "46_42") (pintype "passive"))
    )
    (net (code "44") (name "/LCD_DATA6") (class "Default")
      (node (ref "LCD") (pin "20") (pinfunction "DB6_20") (pintype "passive"))
      (node (ref "P8") (pin "39") (pinfunction "20_39") (pintype "passive"))
    )
    (net (code "45") (name "/LCD_DATA7") (class "Default")
      (node (ref "LCD") (pin "21") (pinfunction "DB7_21") (pintype "passive"))
      (node (ref "P8") (pin "40") (pinfunction "45_40") (pintype "passive"))
    )
    (net (code "46") (name "/LCD_DATA8") (class "Default")
      (node (ref "LCD") (pin "22") (pinfunction "DB8_22") (pintype "passive"))
      (node (ref "P8") (pin "37") (pinfunction "19_37") (pintype "passive"))
    )
    (net (code "47") (name "/LCD_DATA9") (class "Default")
      (node (ref "LCD") (pin "23") (pinfunction "DB9_23") (pintype "passive"))
      (node (ref "P8") (pin "38") (pinfunction "44_38") (pintype "passive"))
    )
    (net (code "48") (name "/LCD_DATA10") (class "Default")
      (node (ref "LCD") (pin "24") (pinfunction "DB10_24") (pintype "passive"))
      (node (ref "P8") (pin "36") (pinfunction "43_36") (pintype "passive"))
    )
    (net (code "49") (name "/LCD_DATA11") (class "Default")
      (node (ref "LCD") (pin "25") (pinfunction "DB11_25") (pintype "passive"))
      (node (ref "P8") (pin "34") (pinfunction "42_34") (pintype "passive"))
    )
    (net (code "50") (name "/LCD_DATA12") (class "Default")
      (node (ref "LCD") (pin "26") (pinfunction "DB12_26") (pintype "passive"))
      (node (ref "P8") (pin "35") (pinfunction "18_35") (pintype "passive"))
    )
    (net (code "51") (name "/LCD_DATA13") (class "Default")
      (node (ref "LCD") (pin "27") (pinfunction "DB13_27") (pintype "passive"))
      (node (ref "P8") (pin "33") (pinfunction "17_33") (pintype "passive"))
    )
    (net (code "52") (name "/LCD_DATA14") (class "Default")
      (node (ref "LCD") (pin "28") (pinfunction "DB14_28") (pintype "passive"))
      (node (ref "P8") (pin "31") (pinfunction "16_31") (pintype "passive"))
    )
    (net (code "53") (name "/LCD_DATA15") (class "Default")
      (node (ref "LCD") (pin "29") (pinfunction "DB15_29") (pintype "passive"))
      (node (ref "P8") (pin "32") (pinfunction "41_32") (pintype "passive"))
    )
    (net (code "54") (name "/LCD_HSYNC") (class "Default")
      (node (ref "LCD") (pin "12") (pinfunction "/WR_12") (pintype "passive"))
      (node (ref "P8") (pin "29") (pinfunction "15_29") (pintype "passive"))
    )
    (net (code "55") (name "/LCD_PCLK") (class "Default")
      (node (ref "LCD") (pin "13") (pinfunction "/RD_13") (pintype "passive"))
      (node (ref "P8") (pin "28") (pinfunction "39_28") (pintype "passive"))
    )
    (net (code "56") (name "/LCD_VSYNC") (class "Default")
      (node (ref "LCD") (pin "11") (pinfunction "D/C_11") (pintype "passive"))
      (node (ref "P8") (pin "27") (pinfunction "14_27") (pintype "passive"))
    )
    (net (code "57") (name "/MUX_SEL0") (class "Default")
      (node (ref "P8") (pin "12") (pinfunction "31_12") (pintype "passive"))
    )
    (net (code "58") (name "/MUX_SEL1") (class "Default")
      (node (ref "P9") (pin "23") (pinfunction "12_23") (pintype "passive"))
    )
    (net (code "59") (name "/MUX_SEL2") (class "Default")
      (node (ref "P9") (pin "27") (pinfunction "14_27") (pintype "passive"))
    )
    (net (code "60") (name "/MUX_SEL3") (class "Default")
      (node (ref "P9") (pin "12") (pinfunction "31_12") (pintype "passive"))
    )
    (net (code "61") (name "/PADN") (class "Default")
      (node (ref "C72") (pin "1") (pinfunction "1_1") (pintype "passive"))
      (node (ref "TMP") (pin "2") (pinfunction "2_2") (pintype "passive"))
      (node (ref "TMP_4C") (pin "2") (pinfunction "DXN_2") (pintype "passive"))
    )
    (net (code "62") (name "/PADP") (class "Default")
      (node (ref "C72") (pin "2") (pinfunction "2_2") (pintype "passive"))
      (node (ref "TMP") (pin "1") (pinfunction "1_1") (pintype "passive"))
      (node (ref "TMP_4C") (pin "1") (pinfunction "DXP_1") (pintype "passive"))
    )
    (net (code "63") (name "/SYS_RESETn") (class "Default")
      (node (ref "LCD") (pin "30") (pinfunction "/RES_30") (pintype "passive"))
      (node (ref "P9") (pin "10") (pinfunction "30_10") (pintype "passive"))
    )
    (net (code "64") (name "GND") (class "Default")
      (node (ref "C10") (pin "1") (pinfunction "1_1") (pintype "passive"))
      (node (ref "C11") (pin "1") (pinfunction "1_1") (pintype "passive"))
      (node (ref "C12") (pin "1") (pinfunction "1_1") (pintype "passive"))
      (node (ref "C14") (pin "1") (pinfunction "1_1") (pintype "passive"))
      (node (ref "C15") (pin "1") (pinfunction "1_1") (pintype "passive"))
      (node (ref "C16") (pin "1") (pinfunction "1_1") (pintype "passive"))
      (node (ref "C18") (pin "1") (pinfunction "1_1") (pintype "passive"))
      (node (ref "C19") (pin "1") (pinfunction "1_1") (pintype "passive"))
      (node (ref "C2") (pin "1") (pinfunction "1_1") (pintype "passive"))
      (node (ref "C20") (pin "1") (pinfunction "1_1") (pintype "passive"))
      (node (ref "C22") (pin "1") (pinfunction "1_1") (pintype "passive"))
      (node (ref "C23") (pin "1") (pinfunction "1_1") (pintype "passive"))
      (node (ref "C24") (pin "1") (pinfunction "1_1") (pintype "passive"))
      (node (ref "C26") (pin "1") (pinfunction "1_1") (pintype "passive"))
      (node (ref "C27") (pin "1") (pinfunction "1_1") (pintype "passive"))
      (node (ref "C28") (pin "1") (pinfunction "1_1") (pintype "passive"))
      (node (ref "C3") (pin "1") (pinfunction "1_1") (pintype "passive"))
      (node (ref "C30") (pin "1") (pinfunction "1_1") (pintype "passive"))
      (node (ref "C31") (pin "1") (pinfunction "1_1") (pintype "passive"))
      (node (ref "C32") (pin "1") (pinfunction "1_1") (pintype "passive"))
      (node (ref "C34") (pin "1") (pinfunction "1_1") (pintype "passive"))
      (node (ref "C35") (pin "1") (pinfunction "1_1") (pintype "passive"))
      (node (ref "C36") (pin "1") (pinfunction "1_1") (pintype "passive"))
      (node (ref "C38") (pin "1") (pinfunction "1_1") (pintype "passive"))
      (node (ref "C39") (pin "1") (pinfunction "1_1") (pintype "passive"))
      (node (ref "C4") (pin "1") (pinfunction "1_1") (pintype "passive"))
      (node (ref "C40") (pin "1") (pinfunction "1_1") (pintype "passive"))
      (node (ref "C42") (pin "1") (pinfunction "1_1") (pintype "passive"))
      (node (ref "C43") (pin "1") (pinfunction "1_1") (pintype "passive"))
      (node (ref "C44") (pin "1") (pinfunction "1_1") (pintype "passive"))
      (node (ref "C46") (pin "1") (pinfunction "1_1") (pintype "passive"))
      (node (ref "C47") (pin "1") (pinfunction "1_1") (pintype "passive"))
      (node (ref "C48") (pin "1") (pinfunction "1_1") (pintype "passive"))
      (node (ref "C50") (pin "1") (pinfunction "1_1") (pintype "passive"))
      (node (ref "C51") (pin "1") (pinfunction "1_1") (pintype "passive"))
      (node (ref "C52") (pin "1") (pinfunction "1_1") (pintype "passive"))
      (node (ref "C6") (pin "1") (pinfunction "1_1") (pintype "passive"))
      (node (ref "C7") (pin "1") (pinfunction "1_1") (pintype "passive"))
      (node (ref "C70") (pin "1") (pinfunction "1_1") (pintype "passive"))
      (node (ref "C71") (pin "1") (pinfunction "1_1") (pintype "passive"))
      (node (ref "C8") (pin "1") (pinfunction "1_1") (pintype "passive"))
      (node (ref "INA_42") (pin "1") (pinfunction "A1_1") (pintype "passive"))
      (node (ref "INA_42") (pin "7") (pinfunction "GND_7") (pintype "passive"))
      (node (ref "INA_43") (pin "1") (pinfunction "A1_1") (pintype "passive"))
      (node (ref "INA_43") (pin "7") (pinfunction "GND_7") (pintype "passive"))
      (node (ref "INA_44") (pin "2") (pinfunction "A0_2") (pintype "passive"))
      (node (ref "INA_44") (pin "7") (pinfunction "GND_7") (pintype "passive"))
      (node (ref "INA_45") (pin "7") (pinfunction "GND_7") (pintype "passive"))
      (node (ref "INA_46") (pin "7") (pinfunction "GND_7") (pintype "passive"))
      (node (ref "INA_47") (pin "7") (pinfunction "GND_7") (pintype "passive"))
      (node (ref "INA_48") (pin "2") (pinfunction "A0_2") (pintype "passive"))
      (node (ref "INA_48") (pin "7") (pinfunction "GND_7") (pintype "passive"))
      (node (ref "INA_49") (pin "7") (pinfunction "GND_7") (pintype "passive"))
      (node (ref "INA_4A") (pin "7") (pinfunction "GND_7") (pintype "passive"))
      (node (ref "INA_4B") (pin "7") (pinfunction "GND_7") (pintype "passive"))
      (node (ref "INA_4D") (pin "7") (pinfunction "GND_7") (pintype "passive"))
      (node (ref "INA_4E") (pin "7") (pinfunction "GND_7") (pintype "passive"))
      (node (ref "INA_4F") (pin "7") (pinfunction "GND_7") (pintype "passive"))
      (node (ref "J1") (pin "1") (pinfunction "1_1") (pintype "passive"))
      (node (ref "LCD") (pin "1") (pinfunction "GND_1") (pintype "passive"))
      (node (ref "LCD") (pin "10") (pinfunction "/CS_10") (pintype "passive"))
      (node (ref "LCD") (pin "33") (pinfunction "GND_33") (pintype "passive"))
      (node (ref "LCD") (pin "34") (pinfunction "LED-K1_34") (pintype "passive"))
      (node (ref "LCD") (pin "35") (pinfunction "LED-K2_35") (pintype "passive"))
      (node (ref "LCD") (pin "36") (pinfunction "LED-K3_36") (pintype "passive"))
      (node (ref "LCD") (pin "37") (pinfunction "LED-K4_37") (pintype "passive"))
      (node (ref "LCD") (pin "39") (pinfunction "GND_39") (pintype "passive"))
      (node (ref "P8") (pin "1") (pinfunction "1_1") (pintype "passive"))
      (node (ref "P8") (pin "2") (pinfunction "26_2") (pintype "passive"))
      (node (ref "P9") (pin "1") (pinfunction "1_1") (pintype "passive"))
      (node (ref "P9") (pin "2") (pinfunction "26_2") (pintype "passive"))
      (node (ref "P9") (pin "43") (pinfunction "22_43") (pintype "passive"))
      (node (ref "P9") (pin "44") (pinfunction "47_44") (pintype "passive"))
      (node (ref "P9") (pin "45") (pinfunction "23_45") (pintype "passive"))
      (node (ref "P9") (pin "46") (pinfunction "48_46") (pintype "passive"))
      (node (ref "PMDC") (pin "3") (pinfunction "3_3") (pintype "passive"))
      (node (ref "TMP_4C") (pin "3") (pinfunction "A1_3") (pintype "passive"))
      (node (ref "TMP_4C") (pin "4") (pinfunction "A0_4") (pintype "passive"))
      (node (ref "TMP_4C") (pin "5") (pinfunction "GND_5") (pintype "power_in"))
    )
    (net (code "65") (name "V3_3D") (class "Default")
      (node (ref "C10") (pin "2") (pinfunction "2_2") (pintype "passive"))
      (node (ref "C11") (pin "2") (pinfunction "2_2") (pintype "passive"))
      (node (ref "C14") (pin "2") (pinfunction "2_2") (pintype "passive"))
      (node (ref "C15") (pin "2") (pinfunction "2_2") (pintype "passive"))
      (node (ref "C18") (pin "2") (pinfunction "2_2") (pintype "passive"))
      (node (ref "C19") (pin "2") (pinfunction "2_2") (pintype "passive"))
      (node (ref "C2") (pin "2") (pinfunction "2_2") (pintype "passive"))
      (node (ref "C22") (pin "2") (pinfunction "2_2") (pintype "passive"))
      (node (ref "C23") (pin "2") (pinfunction "2_2") (pintype "passive"))
      (node (ref "C26") (pin "2") (pinfunction "2_2") (pintype "passive"))
      (node (ref "C27") (pin "2") (pinfunction "2_2") (pintype "passive"))
      (node (ref "C3") (pin "2") (pinfunction "2_2") (pintype "passive"))
      (node (ref "C30") (pin "2") (pinfunction "2_2") (pintype "passive"))
      (node (ref "C31") (pin "2") (pinfunction "2_2") (pintype "passive"))
      (node (ref "C34") (pin "2") (pinfunction "2_2") (pintype "passive"))
      (node (ref "C35") (pin "2") (pinfunction "2_2") (pintype "passive"))
      (node (ref "C38") (pin "2") (pinfunction "2_2") (pintype "passive"))
      (node (ref "C39") (pin "2") (pinfunction "2_2") (pintype "passive"))
      (node (ref "C42") (pin "2") (pinfunction "2_2") (pintype "passive"))
      (node (ref "C43") (pin "2") (pinfunction "2_2") (pintype "passive"))
      (node (ref "C46") (pin "2") (pinfunction "2_2") (pintype "passive"))
      (node (ref "C47") (pin "2") (pinfunction "2_2") (pintype "passive"))
      (node (ref "C50") (pin "2") (pinfunction "2_2") (pintype "passive"))
      (node (ref "C51") (pin "2") (pinfunction "2_2") (pintype "passive"))
      (node (ref "C6") (pin "2") (pinfunction "2_2") (pintype "passive"))
      (node (ref "C7") (pin "2") (pinfunction "2_2") (pintype "passive"))
      (node (ref "C70") (pin "2") (pinfunction "2_2") (pintype "passive"))
      (node (ref "C71") (pin "2") (pinfunction "2_2") (pintype "passive"))
      (node (ref "INA_42") (pin "6") (pinfunction "VS_6") (pintype "passive"))
      (node (ref "INA_43") (pin "6") (pinfunction "VS_6") (pintype "passive"))
      (node (ref "INA_44") (pin "1") (pinfunction "A1_1") (pintype "passive"))
      (node (ref "INA_44") (pin "6") (pinfunction "VS_6") (pintype "passive"))
      (node (ref "INA_45") (pin "1") (pinfunction "A1_1") (pintype "passive"))
      (node (ref "INA_45") (pin "2") (pinfunction "A0_2") (pintype "passive"))
      (node (ref "INA_45") (pin "6") (pinfunction "VS_6") (pintype "passive"))
      (node (ref "INA_46") (pin "1") (pinfunction "A1_1") (pintype "passive"))
      (node (ref "INA_46") (pin "6") (pinfunction "VS_6") (pintype "passive"))
      (node (ref "INA_47") (pin "1") (pinfunction "A1_1") (pintype "passive"))
      (node (ref "INA_47") (pin "6") (pinfunction "VS_6") (pintype "passive"))
      (node (ref "INA_48") (pin "6") (pinfunction "VS_6") (pintype "passive"))
      (node (ref "INA_49") (pin "2") (pinfunction "A0_2") (pintype "passive"))
      (node (ref "INA_49") (pin "6") (pinfunction "VS_6") (pintype "passive"))
      (node (ref "INA_4A") (pin "6") (pinfunction "VS_6") (pintype "passive"))
      (node (ref "INA_4B") (pin "6") (pinfunction "VS_6") (pintype "passive"))
      (node (ref "INA_4D") (pin "2") (pinfunction "A0_2") (pintype "passive"))
      (node (ref "INA_4D") (pin "6") (pinfunction "VS_6") (pintype "passive"))
      (node (ref "INA_4E") (pin "6") (pinfunction "VS_6") (pintype "passive"))
      (node (ref "INA_4F") (pin "6") (pinfunction "VS_6") (pintype "passive"))
      (node (ref "LCD") (pin "38") (pinfunction "LED-A_38") (pintype "passive"))
      (node (ref "LCD") (pin "7") (pinfunction "VDD_7") (pintype "passive"))
      (node (ref "LCD") (pin "8") (pinfunction "IOVDD_8") (pintype "passive"))
      (node (ref "P9") (pin "3") (pinfunction "2_3") (pintype "passive"))
      (node (ref "P9") (pin "4") (pinfunction "27_4") (pintype "passive"))
      (node (ref "PMDC") (pin "5") (pinfunction "5_5") (pintype "passive"))
      (node (ref "R3") (pin "2") (pinfunction "2_2") (pintype "passive"))
      (node (ref "R4") (pin "2") (pinfunction "2_2") (pintype "passive"))
      (node (ref "TMP_4C") (pin "8") (pinfunction "V+_8") (pintype "power_in"))
    )
    (net (code "66") (name "unconnected-(INA_4A-Alert-Pad3)") (class "Default")
      (node (ref "INA_4A") (pin "3") (pinfunction "Alert_3") (pintype "passive"))
    )
    (net (code "67") (name "unconnected-(INA_4B-Alert-Pad3)") (class "Default")
      (node (ref "INA_4B") (pin "3") (pinfunction "Alert_3") (pintype "passive"))
    )
    (net (code "68") (name "unconnected-(INA_4D-Alert-Pad3)") (class "Default")
      (node (ref "INA_4D") (pin "3") (pinfunction "Alert_3") (pintype "passive"))
    )
    (net (code "69") (name "unconnected-(INA_4E-Alert-Pad3)") (class "Default")
      (node (ref "INA_4E") (pin "3") (pinfunction "Alert_3") (pintype "passive"))
    )
    (net (code "70") (name "unconnected-(INA_4F-Alert-Pad3)") (class "Default")
      (node (ref "INA_4F") (pin "3") (pinfunction "Alert_3") (pintype "passive"))
    )
    (net (code "71") (name "unconnected-(INA_42-Alert-Pad3)") (class "Default")
      (node (ref "INA_42") (pin "3") (pinfunction "Alert_3") (pintype "passive"))
    )
    (net (code "72") (name "unconnected-(INA_43-Alert-Pad3)") (class "Default")
      (node (ref "INA_43") (pin "3") (pinfunction "Alert_3") (pintype "passive"))
    )
    (net (code "73") (name "unconnected-(INA_44-Alert-Pad3)") (class "Default")
      (node (ref "INA_44") (pin "3") (pinfunction "Alert_3") (pintype "passive"))
    )
    (net (code "74") (name "unconnected-(INA_45-Alert-Pad3)") (class "Default")
      (node (ref "INA_45") (pin "3") (pinfunction "Alert_3") (pintype "passive"))
    )
    (net (code "75") (name "unconnected-(INA_46-Alert-Pad3)") (class "Default")
      (node (ref "INA_46") (pin "3") (pinfunction "Alert_3") (pintype "passive"))
    )
    (net (code "76") (name "unconnected-(INA_47-Alert-Pad3)") (class "Default")
      (node (ref "INA_47") (pin "3") (pinfunction "Alert_3") (pintype "passive"))
    )
    (net (code "77") (name "unconnected-(INA_48-Alert-Pad3)") (class "Default")
      (node (ref "INA_48") (pin "3") (pinfunction "Alert_3") (pintype "passive"))
    )
    (net (code "78") (name "unconnected-(INA_49-Alert-Pad3)") (class "Default")
      (node (ref "INA_49") (pin "3") (pinfunction "Alert_3") (pintype "passive"))
    )
    (net (code "79") (name "unconnected-(J1-Pad2)") (class "Default")
      (node (ref "J1") (pin "2") (pinfunction "2_2") (pintype "passive"))
    )
    (net (code "80") (name "unconnected-(J1-Pad3)") (class "Default")
      (node (ref "J1") (pin "3") (pinfunction "3_3") (pintype "passive"))
    )
    (net (code "81") (name "unconnected-(J1-Pad6)") (class "Default")
      (node (ref "J1") (pin "6") (pinfunction "6_6") (pintype "passive"))
    )
    (net (code "82") (name "unconnected-(LCD-IM0-Pad31)") (class "Default")
      (node (ref "LCD") (pin "31") (pinfunction "IM0_31") (pintype "passive"))
    )
    (net (code "83") (name "unconnected-(LCD-NC-Pad6)") (class "Default")
      (node (ref "LCD") (pin "6") (pinfunction "NC_6") (pintype "passive"))
    )
    (net (code "84") (name "unconnected-(LCD-NC-Pad9)") (class "Default")
      (node (ref "LCD") (pin "9") (pinfunction "NC_9") (pintype "passive"))
    )
    (net (code "85") (name "unconnected-(LCD-NC-Pad32)") (class "Default")
      (node (ref "LCD") (pin "32") (pinfunction "NC_32") (pintype "passive"))
    )
    (net (code "86") (name "unconnected-(LCD-NC-Pad40)") (class "Default")
      (node (ref "LCD") (pin "40") (pinfunction "NC_40") (pintype "passive"))
    )
    (net (code "87") (name "unconnected-(P8-2-Pad3)") (class "Default")
      (node (ref "P8") (pin "3") (pinfunction "2_3") (pintype "passive"))
    )
    (net (code "88") (name "unconnected-(P8-3-Pad5)") (class "Default")
      (node (ref "P8") (pin "5") (pinfunction "3_5") (pintype "passive"))
    )
    (net (code "89") (name "unconnected-(P8-4-Pad7)") (class "Default")
      (node (ref "P8") (pin "7") (pinfunction "4_7") (pintype "passive"))
    )
    (net (code "90") (name "unconnected-(P8-5-Pad9)") (class "Default")
      (node (ref "P8") (pin "9") (pinfunction "5_9") (pintype "passive"))
    )
    (net (code "91") (name "unconnected-(P8-6-Pad11)") (class "Default")
      (node (ref "P8") (pin "11") (pinfunction "6_11") (pintype "passive"))
    )
    (net (code "92") (name "unconnected-(P8-7-Pad13)") (class "Default")
      (node (ref "P8") (pin "13") (pinfunction "7_13") (pintype "passive"))
    )
    (net (code "93") (name "unconnected-(P8-8-Pad15)") (class "Default")
      (node (ref "P8") (pin "15") (pinfunction "8_15") (pintype "passive"))
    )
    (net (code "94") (name "unconnected-(P8-9-Pad17)") (class "Default")
      (node (ref "P8") (pin "17") (pinfunction "9_17") (pintype "passive"))
    )
    (net (code "95") (name "unconnected-(P8-10-Pad19)") (class "Default")
      (node (ref "P8") (pin "19") (pinfunction "10_19") (pintype "passive"))
    )
    (net (code "96") (name "unconnected-(P8-11-Pad21)") (class "Default")
      (node (ref "P8") (pin "21") (pinfunction "11_21") (pintype "passive"))
    )
    (net (code "97") (name "unconnected-(P8-12-Pad23)") (class "Default")
      (node (ref "P8") (pin "23") (pinfunction "12_23") (pintype "passive"))
    )
    (net (code "98") (name "unconnected-(P8-13-Pad25)") (class "Default")
      (node (ref "P8") (pin "25") (pinfunction "13_25") (pintype "passive"))
    )
    (net (code "99") (name "unconnected-(P8-27-Pad4)") (class "Default")
      (node (ref "P8") (pin "4") (pinfunction "27_4") (pintype "passive"))
    )
    (net (code "100") (name "unconnected-(P8-28-Pad6)") (class "Default")
      (node (ref "P8") (pin "6") (pinfunction "28_6") (pintype "passive"))
    )
    (net (code "101") (name "unconnected-(P8-29-Pad8)") (class "Default")
      (node (ref "P8") (pin "8") (pinfunction "29_8") (pintype "passive"))
    )
    (net (code "102") (name "unconnected-(P8-30-Pad10)") (class "Default")
      (node (ref "P8") (pin "10") (pinfunction "30_10") (pintype "passive"))
    )
    (net (code "103") (name "unconnected-(P8-32-Pad14)") (class "Default")
      (node (ref "P8") (pin "14") (pinfunction "32_14") (pintype "passive"))
    )
    (net (code "104") (name "unconnected-(P8-33-Pad16)") (class "Default")
      (node (ref "P8") (pin "16") (pinfunction "33_16") (pintype "passive"))
    )
    (net (code "105") (name "unconnected-(P8-34-Pad18)") (class "Default")
      (node (ref "P8") (pin "18") (pinfunction "34_18") (pintype "passive"))
    )
    (net (code "106") (name "unconnected-(P8-35-Pad20)") (class "Default")
      (node (ref "P8") (pin "20") (pinfunction "35_20") (pintype "passive"))
    )
    (net (code "107") (name "unconnected-(P8-36-Pad22)") (class "Default")
      (node (ref "P8") (pin "22") (pinfunction "36_22") (pintype "passive"))
    )
    (net (code "108") (name "unconnected-(P8-37-Pad24)") (class "Default")
      (node (ref "P8") (pin "24") (pinfunction "37_24") (pintype "passive"))
    )
    (net (code "109") (name "unconnected-(P8-38-Pad26)") (class "Default")
      (node (ref "P8") (pin "26") (pinfunction "38_26") (pintype "passive"))
    )
    (net (code "110") (name "unconnected-(P8-40-Pad30)") (class "Default")
      (node (ref "P8") (pin "30") (pinfunction "40_30") (pintype "passive"))
    )
    (net (code "111") (name "unconnected-(P9-3-Pad5)") (class "Default")
      (node (ref "P9") (pin "5") (pinfunction "3_5") (pintype "passive"))
    )
    (net (code "112") (name "unconnected-(P9-4-Pad7)") (class "Default")
      (node (ref "P9") (pin "7") (pinfunction "4_7") (pintype "passive"))
    )
    (net (code "113") (name "unconnected-(P9-5-Pad9)") (class "Default")
      (node (ref "P9") (pin "9") (pinfunction "5_9") (pintype "passive"))
    )
    (net (code "114") (name "unconnected-(P9-6-Pad11)") (class "Default")
      (node (ref "P9") (pin "11") (pinfunction "6_11") (pintype "passive"))
    )
    (net (code "115") (name "unconnected-(P9-7-Pad13)") (class "Default")
      (node (ref "P9") (pin "13") (pinfunction "7_13") (pintype "passive"))
    )
    (net (code "116") (name "unconnected-(P9-8-Pad15)") (class "Default")
      (node (ref "P9") (pin "15") (pinfunction "8_15") (pintype "passive"))
    )
    (net (code "117") (name "unconnected-(P9-11-Pad21)") (class "Default")
      (node (ref "P9") (pin "21") (pinfunction "11_21") (pintype "passive"))
    )
    (net (code "118") (name "unconnected-(P9-13-Pad25)") (class "Default")
      (node (ref "P9") (pin "25") (pinfunction "13_25") (pintype "passive"))
    )
    (net (code "119") (name "unconnected-(P9-15-Pad29)") (class "Default")
      (node (ref "P9") (pin "29") (pinfunction "15_29") (pintype "passive"))
    )
    (net (code "120") (name "unconnected-(P9-16-Pad31)") (class "Default")
      (node (ref "P9") (pin "31") (pinfunction "16_31") (pintype "passive"))
    )
    (net (code "121") (name "unconnected-(P9-17-Pad33)") (class "Default")
      (node (ref "P9") (pin "33") (pinfunction "17_33") (pintype "passive"))
    )
    (net (code "122") (name "unconnected-(P9-18-Pad35)") (class "Default")
      (node (ref "P9") (pin "35") (pinfunction "18_35") (pintype "passive"))
    )
    (net (code "123") (name "unconnected-(P9-21-Pad41)") (class "Default")
      (node (ref "P9") (pin "41") (pinfunction "21_41") (pintype "passive"))
    )
    (net (code "124") (name "unconnected-(P9-28-Pad6)") (class "Default")
      (node (ref "P9") (pin "6") (pinfunction "28_6") (pintype "passive"))
    )
    (net (code "125") (name "unconnected-(P9-29-Pad8)") (class "Default")
      (node (ref "P9") (pin "8") (pinfunction "29_8") (pintype "passive"))
    )
    (net (code "126") (name "unconnected-(P9-32-Pad14)") (class "Default")
      (node (ref "P9") (pin "14") (pinfunction "32_14") (pintype "passive"))
    )
    (net (code "127") (name "unconnected-(P9-33-Pad16)") (class "Default")
      (node (ref "P9") (pin "16") (pinfunction "33_16") (pintype "passive"))
    )
    (net (code "128") (name "unconnected-(P9-36-Pad22)") (class "Default")
      (node (ref "P9") (pin "22") (pinfunction "36_22") (pintype "passive"))
    )
    (net (code "129") (name "unconnected-(P9-37-Pad24)") (class "Default")
      (node (ref "P9") (pin "24") (pinfunction "37_24") (pintype "passive"))
    )
    (net (code "130") (name "unconnected-(P9-38-Pad26)") (class "Default")
      (node (ref "P9") (pin "26") (pinfunction "38_26") (pintype "passive"))
    )
    (net (code "131") (name "unconnected-(P9-39-Pad28)") (class "Default")
      (node (ref "P9") (pin "28") (pinfunction "39_28") (pintype "passive"))
    )
    (net (code "132") (name "unconnected-(P9-40-Pad30)") (class "Default")
      (node (ref "P9") (pin "30") (pinfunction "40_30") (pintype "passive"))
    )
    (net (code "133") (name "unconnected-(P9-41-Pad32)") (class "Default")
      (node (ref "P9") (pin "32") (pinfunction "41_32") (pintype "passive"))
    )
    (net (code "134") (name "unconnected-(P9-42-Pad34)") (class "Default")
      (node (ref "P9") (pin "34") (pinfunction "42_34") (pintype "passive"))
    )
    (net (code "135") (name "unconnected-(P9-43-Pad36)") (class "Default")
      (node (ref "P9") (pin "36") (pinfunction "43_36") (pintype "passive"))
    )
    (net (code "136") (name "unconnected-(P9-46-Pad42)") (class "Default")
      (node (ref "P9") (pin "42") (pinfunction "46_42") (pintype "passive"))
    )
  )
)
